# dsp.net
KiCad netlist of a schematic drawn in Altium Designer
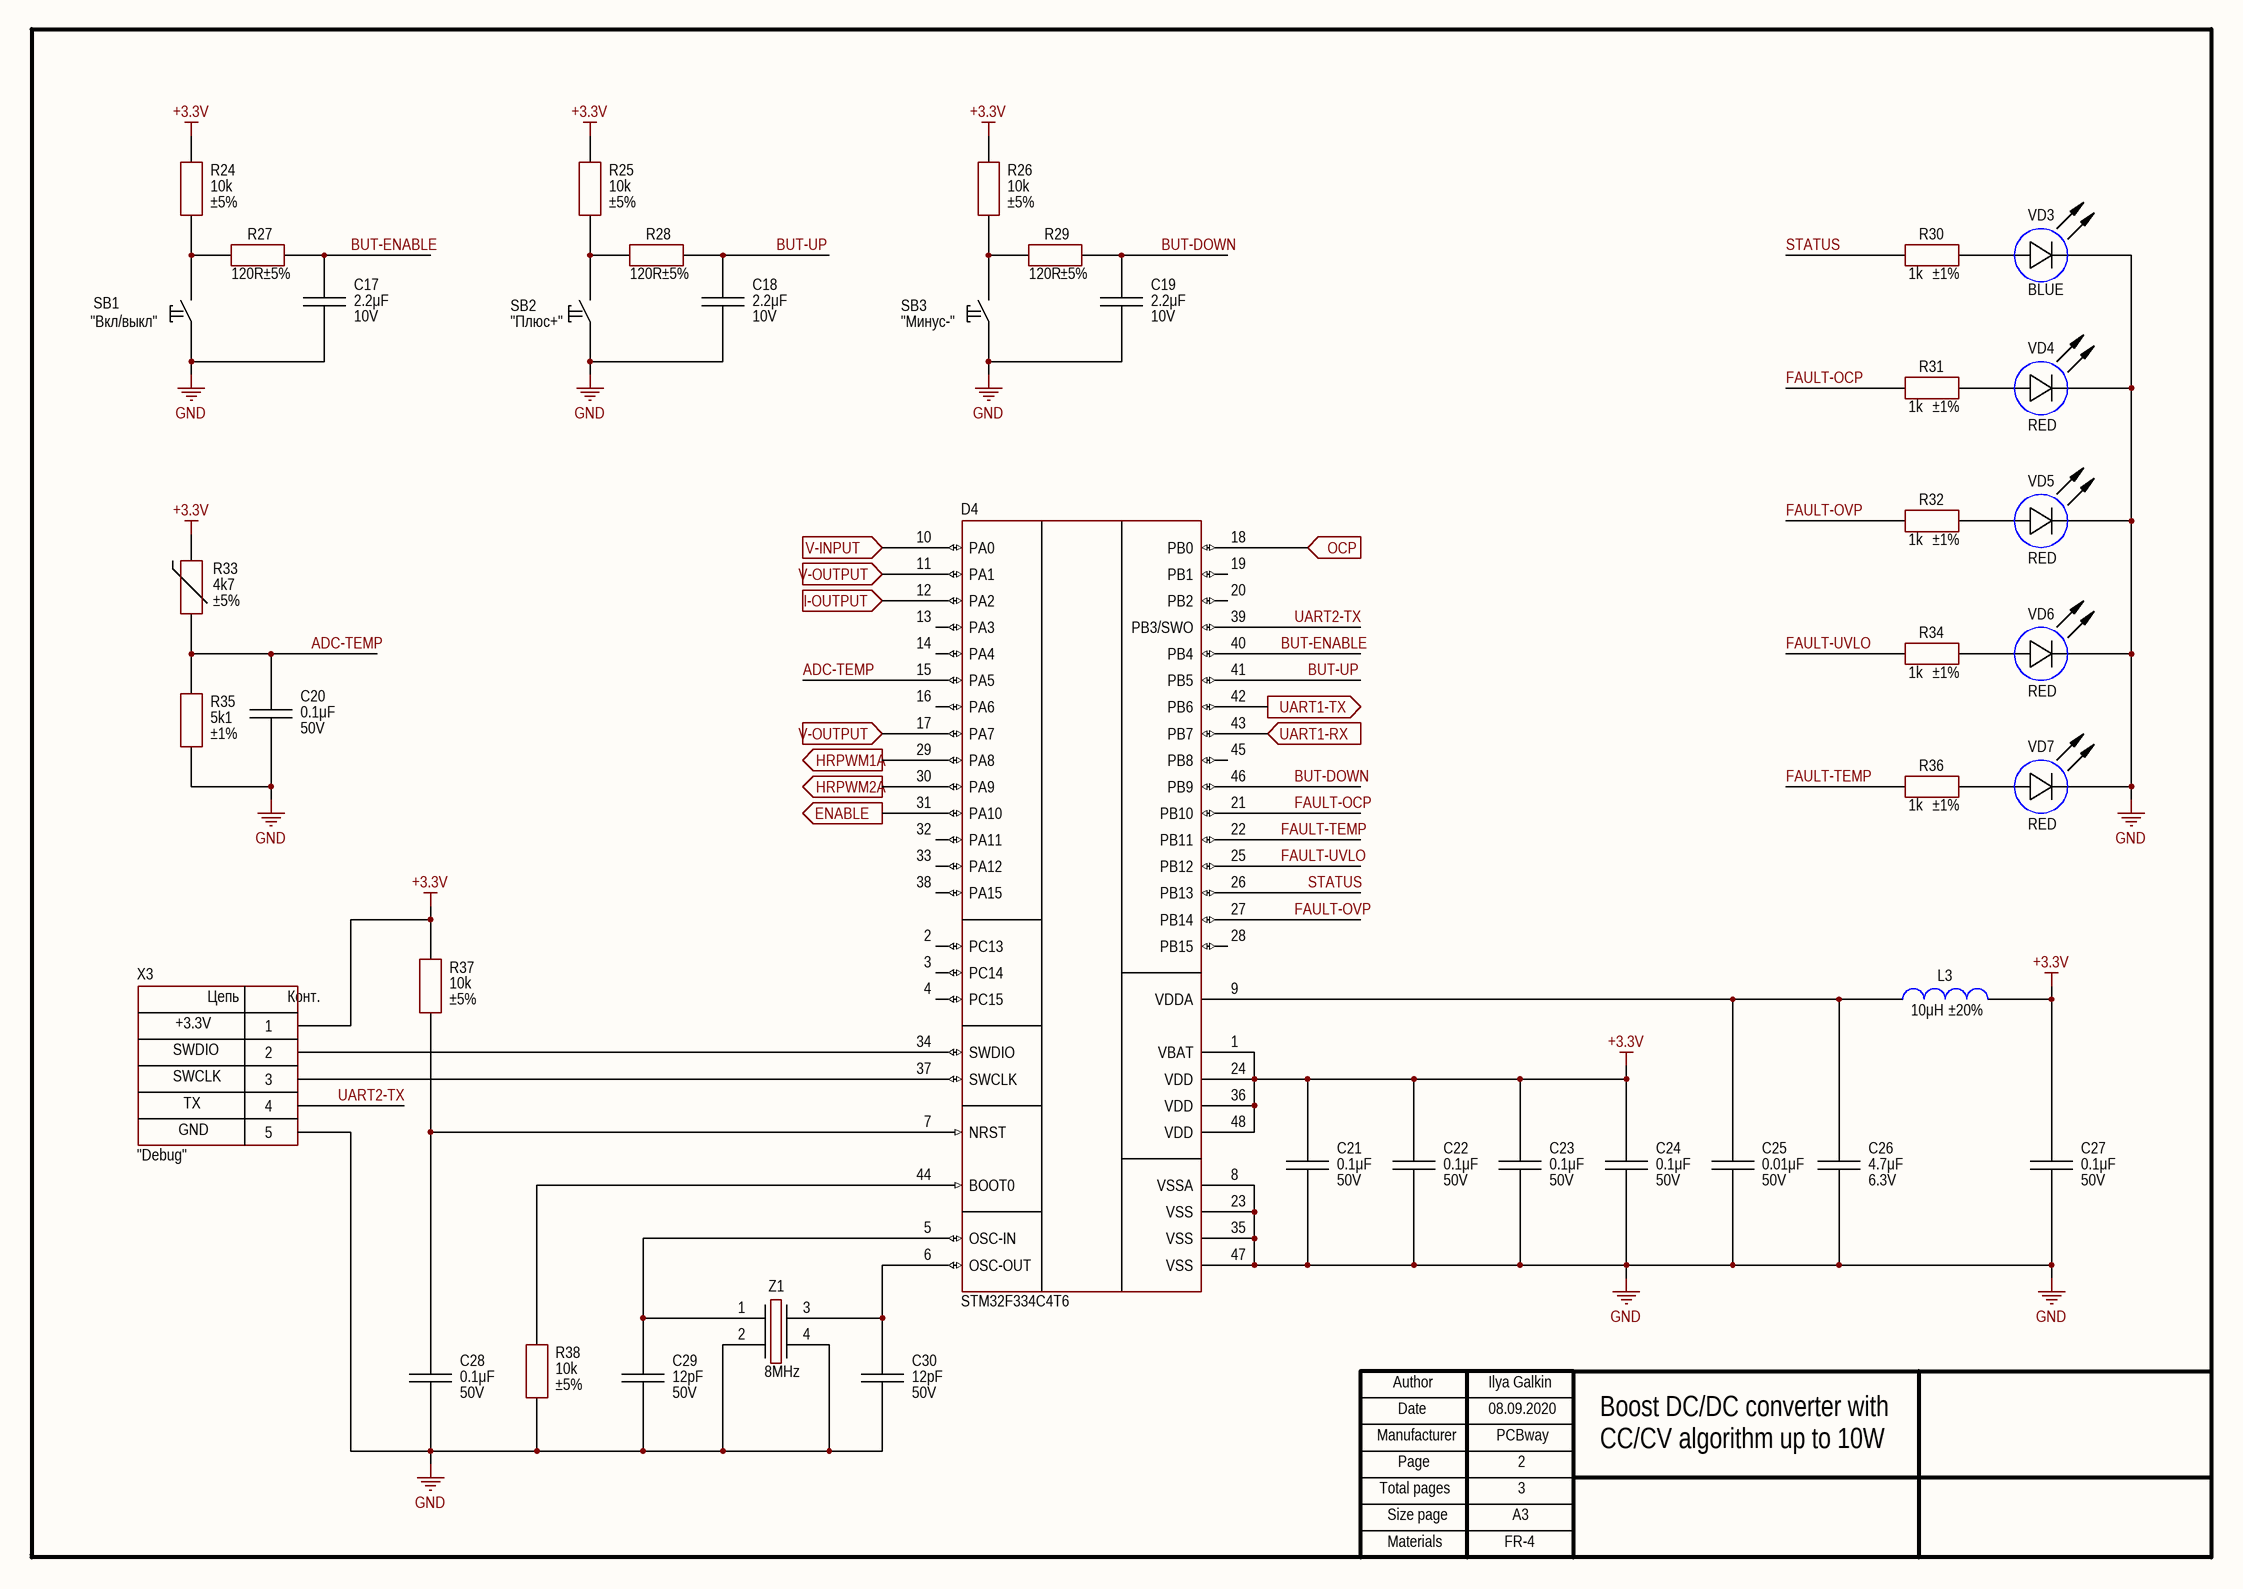
[diagram p0: dsp.SchDoc]

(export (version "E")
  (design (tool "Eeschema 10.0.6"))
  (components
    (comp (ref "C17")
      (value "2.2μF")
      (footprint "CAP: 0603")
      (fields
        (field (name "MANUFACTURER") "Samsung")
        (field (name "PARTNUMBER") "CL10B225KP8NFNC")
        (field (name "VALUEMANUFACTURERPARTNUMBER") "Ceramic capacitor, 2.2μF, X7R, ±10%, 10V, 0603, -55...+125°C")
        (field (name "VOLTAGE") "10V")
      )
      (libsource (lib "capacitor") (part "Ceramic_0603"))
    )
    (comp (ref "C18")
      (value "2.2μF")
      (footprint "CAP: 0603")
      (fields
        (field (name "MANUFACTURER") "Samsung")
        (field (name "PARTNUMBER") "CL10B225KP8NFNC")
        (field (name "VALUEMANUFACTURERPARTNUMBER") "Ceramic capacitor, 2.2μF, X7R, ±10%, 10V, 0603, -55...+125°C")
        (field (name "VOLTAGE") "10V")
      )
      (libsource (lib "capacitor") (part "Ceramic_0603"))
    )
    (comp (ref "C19")
      (value "2.2μF")
      (footprint "CAP: 0603")
      (fields
        (field (name "MANUFACTURER") "Samsung")
        (field (name "PARTNUMBER") "CL10B225KP8NFNC")
        (field (name "VALUEMANUFACTURERPARTNUMBER") "Ceramic capacitor, 2.2μF, X7R, ±10%, 10V, 0603, -55...+125°C")
        (field (name "VOLTAGE") "10V")
      )
      (libsource (lib "capacitor") (part "Ceramic_0603"))
    )
    (comp (ref "C20")
      (value "0.1μF")
      (footprint "CAP: 0603")
      (fields
        (field (name "MANUFACTURER") "Samsung")
        (field (name "PARTNUMBER") "CL10B104KB8NNNL")
        (field (name "VALUEMANUFACTURERPARTNUMBER") "Ceramic capacitor, 0.1μF, X7R, ±10%, 50V, 0603, -55...+125°C")
        (field (name "VOLTAGE") "50V")
      )
      (libsource (lib "capacitor") (part "Ceramic_0603"))
    )
    (comp (ref "C21")
      (value "0.1μF")
      (footprint "CAP: 0603")
      (fields
        (field (name "MANUFACTURER") "Samsung")
        (field (name "PARTNUMBER") "CL10B104KB8NNNL")
        (field (name "VALUEMANUFACTURERPARTNUMBER") "Ceramic capacitor, 0.1μF, X7R, ±10%, 50V, 0603, -55...+125°C")
        (field (name "VOLTAGE") "50V")
      )
      (libsource (lib "capacitor") (part "Ceramic_0603"))
    )
    (comp (ref "C22")
      (value "0.1μF")
      (footprint "CAP: 0603")
      (fields
        (field (name "MANUFACTURER") "Samsung")
        (field (name "PARTNUMBER") "CL10B104KB8NNNL")
        (field (name "VALUEMANUFACTURERPARTNUMBER") "Ceramic capacitor, 0.1μF, X7R, ±10%, 50V, 0603, -55...+125°C")
        (field (name "VOLTAGE") "50V")
      )
      (libsource (lib "capacitor") (part "Ceramic_0603"))
    )
    (comp (ref "C23")
      (value "0.1μF")
      (footprint "CAP: 0603")
      (fields
        (field (name "MANUFACTURER") "Samsung")
        (field (name "PARTNUMBER") "CL10B104KB8NNNL")
        (field (name "VALUEMANUFACTURERPARTNUMBER") "Ceramic capacitor, 0.1μF, X7R, ±10%, 50V, 0603, -55...+125°C")
        (field (name "VOLTAGE") "50V")
      )
      (libsource (lib "capacitor") (part "Ceramic_0603"))
    )
    (comp (ref "C24")
      (value "0.1μF")
      (footprint "CAP: 0603")
      (fields
        (field (name "MANUFACTURER") "Samsung")
        (field (name "PARTNUMBER") "CL10B104KB8NNNL")
        (field (name "VALUEMANUFACTURERPARTNUMBER") "Ceramic capacitor, 0.1μF, X7R, ±10%, 50V, 0603, -55...+125°C")
        (field (name "VOLTAGE") "50V")
      )
      (libsource (lib "capacitor") (part "Ceramic_0603"))
    )
    (comp (ref "C25")
      (value "0.01μF")
      (footprint "CAP: 0603")
      (fields
        (field (name "MANUFACTURER") "Samsung")
        (field (name "PARTNUMBER") "CL10B103KB8NNNC")
        (field (name "VALUEMANUFACTURERPARTNUMBER") "Ceramic capacitor, 0.01μF, X7R, ±10%, 50V, 0603, -55...+125°C")
        (field (name "VOLTAGE") "50V")
      )
      (libsource (lib "capacitor") (part "Ceramic_0603"))
    )
    (comp (ref "C26")
      (value "4.7μF")
      (footprint "CAP: 0603")
      (fields
        (field (name "MANUFACTURER") "Samsung")
        (field (name "PARTNUMBER") "CL10B475KQ8NQNC")
        (field (name "VALUEMANUFACTURERPARTNUMBER") "Ceramic capacitor, 4.7μF, X7R, ±10%, 6.3V, 0603, -55...+125°C")
        (field (name "VOLTAGE") "6.3V")
      )
      (libsource (lib "capacitor") (part "Ceramic_0603"))
    )
    (comp (ref "C27")
      (value "0.1μF")
      (footprint "CAP: 0603")
      (fields
        (field (name "MANUFACTURER") "Samsung")
        (field (name "PARTNUMBER") "CL10B104KB8NNNL")
        (field (name "VALUEMANUFACTURERPARTNUMBER") "Ceramic capacitor, 0.1μF, X7R, ±10%, 50V, 0603, -55...+125°C")
        (field (name "VOLTAGE") "50V")
      )
      (libsource (lib "capacitor") (part "Ceramic_0603"))
    )
    (comp (ref "C28")
      (value "0.1μF")
      (footprint "CAP: 0603")
      (fields
        (field (name "MANUFACTURER") "Samsung")
        (field (name "PARTNUMBER") "CL10B104KB8NNNL")
        (field (name "VALUEMANUFACTURERPARTNUMBER") "Ceramic capacitor, 0.1μF, X7R, ±10%, 50V, 0603, -55...+125°C")
        (field (name "VOLTAGE") "50V")
      )
      (libsource (lib "capacitor") (part "Ceramic_0603"))
    )
    (comp (ref "C29")
      (value "12pF")
      (footprint "CAP: 0603")
      (fields
        (field (name "MANUFACTURER") "Samsung")
        (field (name "PARTNUMBER") "CL10C120JB8NNNC")
        (field (name "VALUEMANUFACTURERPARTNUMBER") "Ceramic capacitor, 12pF, NPO, ±10%, 50V, 0603, -55...+125°C")
        (field (name "VOLTAGE") "50V")
      )
      (libsource (lib "Capacitor") (part "Ceramic_0603"))
    )
    (comp (ref "C30")
      (value "12pF")
      (footprint "CAP: 0603")
      (fields
        (field (name "MANUFACTURER") "Samsung")
        (field (name "PARTNUMBER") "CL10C120JB8NNNC")
        (field (name "VALUEMANUFACTURERPARTNUMBER") "Ceramic capacitor, 12pF, NPO, ±10%, 50V, 0603, -55...+125°C")
        (field (name "VOLTAGE") "50V")
      )
      (libsource (lib "Capacitor") (part "Ceramic_0603"))
    )
    (comp (ref "D4")
      (value "~")
      (footprint "48-LQFP")
      (description "Cortex-M4")
      (fields
        (field (name "MANUFACTURER") "STMicroelectronics")
        (field (name "VALUEMANUFACTURERPARTNUMBER") "IC microcontroller, 32-Bit, Cortex-M4, 72MHz, 64KB, 12KB, 2...3.6V, -40...+85°C, 48-LQFP")
        (field (name "PARTNUMBER") "STM32F334C4T6")
      )
      (libsource (lib "ic-mcu") (part "STM32F334C8T6"))
    )
    (comp (ref "L3")
      (value "10μH")
      (footprint "IND: 0603")
      (fields
        (field (name "MANUFACTURER") "Murata Electronics")
        (field (name "PARTNUMBER") "LQM18FN100M00D")
        (field (name "VALUEMANUFACTURERPARTNUMBER") "Fixed inductor, 10μH, ±20%, 0603, 50mA, -55...+125°C")
        (field (name "TOLERANCE") "±20%")
      )
      (libsource (lib "Inductor") (part "Inductor_0603"))
    )
    (comp (ref "R24")
      (value "10k")
      (footprint "RES: 0603")
      (fields
        (field (name "MANUFACTURER") "Yageo")
        (field (name "PARTNUMBER") "RC0603JR-0710KL")
        (field (name "VALUEMANUFACTURERPARTNUMBER") "Resistor film, 10k, ±5%, 0603, 0.1W, -55...+125°C")
        (field (name "TOLERANCE") "±5%")
      )
      (libsource (lib "resistor") (part "Resistor_0603"))
    )
    (comp (ref "R25")
      (value "10k")
      (footprint "RES: 0603")
      (fields
        (field (name "MANUFACTURER") "Yageo")
        (field (name "PARTNUMBER") "RC0603JR-0710KL")
        (field (name "VALUEMANUFACTURERPARTNUMBER") "Resistor film, 10k, ±5%, 0603, 0.1W, -55...+125°C")
        (field (name "TOLERANCE") "±5%")
      )
      (libsource (lib "resistor") (part "Resistor_0603"))
    )
    (comp (ref "R26")
      (value "10k")
      (footprint "RES: 0603")
      (fields
        (field (name "MANUFACTURER") "Yageo")
        (field (name "PARTNUMBER") "RC0603JR-0710KL")
        (field (name "VALUEMANUFACTURERPARTNUMBER") "Resistor film, 10k, ±5%, 0603, 0.1W, -55...+125°C")
        (field (name "TOLERANCE") "±5%")
      )
      (libsource (lib "resistor") (part "Resistor_0603"))
    )
    (comp (ref "R27")
      (value "120R")
      (footprint "RES: 0603")
      (fields
        (field (name "MANUFACTURER") "Yageo")
        (field (name "PARTNUMBER") "RC0603JR-07120RL")
        (field (name "VALUEMANUFACTURERPARTNUMBER") "Resistor film, 120R, ±5%, 0603, 0.1W, -55...+125°C")
        (field (name "TOLERANCE") "±5%")
      )
      (libsource (lib "") (part "Resistor_0603_1"))
    )
    (comp (ref "R28")
      (value "120R")
      (footprint "RES: 0603")
      (fields
        (field (name "MANUFACTURER") "Yageo")
        (field (name "PARTNUMBER") "RC0603JR-07120RL")
        (field (name "VALUEMANUFACTURERPARTNUMBER") "Resistor film, 120R, ±5%, 0603, 0.1W, -55...+125°C")
        (field (name "TOLERANCE") "±5%")
      )
      (libsource (lib "") (part "Resistor_0603_1"))
    )
    (comp (ref "R29")
      (value "120R")
      (footprint "RES: 0603")
      (fields
        (field (name "MANUFACTURER") "Yageo")
        (field (name "PARTNUMBER") "RC0603JR-07120RL")
        (field (name "VALUEMANUFACTURERPARTNUMBER") "Resistor film, 120R, ±5%, 0603, 0.1W, -55...+125°C")
        (field (name "TOLERANCE") "±5%")
      )
      (libsource (lib "") (part "Resistor_0603_1"))
    )
    (comp (ref "R30")
      (value "1k")
      (footprint "RES: 0603")
      (fields
        (field (name "MANUFACTURER") "Yageo")
        (field (name "PARTNUMBER") "RC0603FR-071KL")
        (field (name "VALUEMANUFACTURERPARTNUMBER") "Resistor film, 1k, ±1%, 0603, 0.1W, -55...+125°C")
        (field (name "TOLERANCE") "±1%")
      )
      (libsource (lib "") (part "Resistor_0603_1"))
    )
    (comp (ref "R31")
      (value "1k")
      (footprint "RES: 0603")
      (fields
        (field (name "MANUFACTURER") "Yageo")
        (field (name "PARTNUMBER") "RC0603FR-071KL")
        (field (name "VALUEMANUFACTURERPARTNUMBER") "Resistor film, 1k, ±1%, 0603, 0.1W, -55...+125°C")
        (field (name "TOLERANCE") "±1%")
      )
      (libsource (lib "") (part "Resistor_0603_1"))
    )
    (comp (ref "R32")
      (value "1k")
      (footprint "RES: 0603")
      (fields
        (field (name "MANUFACTURER") "Yageo")
        (field (name "PARTNUMBER") "RC0603FR-071KL")
        (field (name "VALUEMANUFACTURERPARTNUMBER") "Resistor film, 1k, ±1%, 0603, 0.1W, -55...+125°C")
        (field (name "TOLERANCE") "±1%")
      )
      (libsource (lib "") (part "Resistor_0603_1"))
    )
    (comp (ref "R33")
      (value "4k7")
      (footprint "RES: 0603")
      (fields
        (field (name "MANUFACTURER") "Murata")
        (field (name "PARTNUMBER") "NCP18XM472J03RB")
        (field (name "VALUEMANUFACTURERPARTNUMBER") "NTC resistor, 4k7, ±5%, 0603, 3500K, -55...+125°C")
        (field (name "TOLERANCE") "±5%")
      )
      (libsource (lib "resistor") (part "NTC"))
    )
    (comp (ref "R34")
      (value "1k")
      (footprint "RES: 0603")
      (fields
        (field (name "MANUFACTURER") "Yageo")
        (field (name "PARTNUMBER") "RC0603FR-071KL")
        (field (name "VALUEMANUFACTURERPARTNUMBER") "Resistor film, 1k, ±1%, 0603, 0.1W, -55...+125°C")
        (field (name "TOLERANCE") "±1%")
      )
      (libsource (lib "") (part "Resistor_0603_1"))
    )
    (comp (ref "R35")
      (value "5k1")
      (footprint "RES: 0603")
      (fields
        (field (name "MANUFACTURER") "Yageo")
        (field (name "PARTNUMBER") "RC0603FR-075K1L")
        (field (name "VALUEMANUFACTURERPARTNUMBER") "Resistor film, 5k1, ±1%, 0603, 0.1W, -55...+125°C")
        (field (name "TOLERANCE") "±1%")
      )
      (libsource (lib "resistor") (part "Resistor_0603"))
    )
    (comp (ref "R36")
      (value "1k")
      (footprint "RES: 0603")
      (fields
        (field (name "MANUFACTURER") "Yageo")
        (field (name "PARTNUMBER") "RC0603FR-071KL")
        (field (name "VALUEMANUFACTURERPARTNUMBER") "Resistor film, 1k, ±1%, 0603, 0.1W, -55...+125°C")
        (field (name "TOLERANCE") "±1%")
      )
      (libsource (lib "") (part "Resistor_0603_1"))
    )
    (comp (ref "R37")
      (value "10k")
      (footprint "RES: 0603")
      (fields
        (field (name "MANUFACTURER") "Yageo")
        (field (name "PARTNUMBER") "RC0603JR-0710KL")
        (field (name "VALUEMANUFACTURERPARTNUMBER") "Resistor film, 10k, ±5%, 0603, 0.1W, -55...+125°C")
        (field (name "TOLERANCE") "±5%")
      )
      (libsource (lib "resistor") (part "Resistor_0603"))
    )
    (comp (ref "R38")
      (value "10k")
      (footprint "RES: 0603")
      (fields
        (field (name "MANUFACTURER") "Yageo")
        (field (name "PARTNUMBER") "RC0603JR-0710KL")
        (field (name "VALUEMANUFACTURERPARTNUMBER") "Resistor film, 10k, ±5%, 0603, 0.1W, -55...+125°C")
        (field (name "TOLERANCE") "±5%")
      )
      (libsource (lib "resistor") (part "Resistor_0603"))
    )
    (comp (ref "SB1")
      (value "~")
      (footprint "BUT: 6x3.5 SMD")
      (fields
        (field (name "MANUFACTURER") "C&K")
        (field (name "VALUEMANUFACTURERPARTNUMBER") "Tactile button, 6x3.5mm")
        (field (name "PARTNUMBER") "PTS636 SM43")
        (field (name "COMMENTTEXT") "\"Вкл/выкл\"")
      )
      (libsource (lib "electromechanics") (part "Button_tactile"))
    )
    (comp (ref "SB2")
      (value "~")
      (footprint "BUT: 6x3.5 SMD")
      (fields
        (field (name "MANUFACTURER") "C&K")
        (field (name "VALUEMANUFACTURERPARTNUMBER") "Tactile button, 6x3.5mm")
        (field (name "PARTNUMBER") "PTS636 SM43")
        (field (name "COMMENTTEXT") "\"Плюс+\"")
      )
      (libsource (lib "electromechanics") (part "Button_tactile"))
    )
    (comp (ref "SB3")
      (value "~")
      (footprint "BUT: 6x3.5 SMD")
      (fields
        (field (name "MANUFACTURER") "C&K")
        (field (name "VALUEMANUFACTURERPARTNUMBER") "Tactile button, 6x3.5mm")
        (field (name "PARTNUMBER") "PTS636 SM43")
        (field (name "COMMENTTEXT") "\"Минус-\"")
      )
      (libsource (lib "electromechanics") (part "Button_tactile"))
    )
    (comp (ref "VD3")
      (value "~")
      (footprint "LED: 0603B")
      (fields
        (field (name "MANUFACTURER") "Wurth")
        (field (name "VALUEMANUFACTURERPARTNUMBER") "LED, 20mA, 3.2V, 0603, -55...+150°C")
        (field (name "PARTNUMBER") "150060BS75000")
        (field (name "COLOR") "BLUE")
      )
      (libsource (lib "Diode") (part "LED_single"))
    )
    (comp (ref "VD4")
      (value "~")
      (footprint "LED: 0603R")
      (fields
        (field (name "MANUFACTURER") "Wurth")
        (field (name "VALUEMANUFACTURERPARTNUMBER") "LED, 20 mA, 2V, 0603, -55...+150°C")
        (field (name "PARTNUMBER") "150060RS75000")
        (field (name "COLOR") "RED")
      )
      (libsource (lib "Diode") (part "LED_single"))
    )
    (comp (ref "VD5")
      (value "~")
      (footprint "LED: 0603R")
      (fields
        (field (name "MANUFACTURER") "Wurth")
        (field (name "VALUEMANUFACTURERPARTNUMBER") "LED, 20 mA, 2V, 0603, -55...+150°C")
        (field (name "PARTNUMBER") "150060RS75000")
        (field (name "COLOR") "RED")
      )
      (libsource (lib "Diode") (part "LED_single"))
    )
    (comp (ref "VD6")
      (value "~")
      (footprint "LED: 0603R")
      (fields
        (field (name "MANUFACTURER") "Wurth")
        (field (name "VALUEMANUFACTURERPARTNUMBER") "LED, 20 mA, 2V, 0603, -55...+150°C")
        (field (name "PARTNUMBER") "150060RS75000")
        (field (name "COLOR") "RED")
      )
      (libsource (lib "Diode") (part "LED_single"))
    )
    (comp (ref "VD7")
      (value "~")
      (footprint "LED: 0603R")
      (fields
        (field (name "MANUFACTURER") "Wurth")
        (field (name "VALUEMANUFACTURERPARTNUMBER") "LED, 20 mA, 2V, 0603, -55...+150°C")
        (field (name "PARTNUMBER") "150060RS75000")
        (field (name "COLOR") "RED")
      )
      (libsource (lib "Diode") (part "LED_single"))
    )
    (comp (ref "X3")
      (value "~")
      (footprint "CON: SM05B-GHS")
      (fields
        (field (name "MANUFACTURER") "JST")
        (field (name "VALUEMANUFACTURERPARTNUMBER") "Connector, 5pin, 1.25mm, 50VDC, 1A")
        (field (name "PARTNUMBER") "SM05B-GHS")
        (field (name "COMMENTTEXT") "\"Debug\"")
      )
      (libsource (lib "Connector") (part "Connector_SM05B"))
    )
    (comp (ref "Z1")
      (value "~")
      (footprint "OSC: 3225")
      (fields
        (field (name "MANUFACTURER") "ECS")
        (field (name "PARTNUMBER") "ECS-80-12-33-JGN-TR")
        (field (name "VALUEMANUFACTURERPARTNUMBER") "Crystal, 8MHz, 12pF, ±30ppm, case 3225, -40...+85°C")
        (field (name "FREQUENCY") "8MHz")
      )
      (libsource (lib "Oscilator") (part "Crystal_3225"))
    )
  )
  (nets
    (net (code "1") (name "+3.3V") (class "Default")
      (node (ref "C21") (pin "2") (pinfunction "2_2") (pintype "passive"))
      (node (ref "C22") (pin "2") (pinfunction "2_2") (pintype "passive"))
      (node (ref "C23") (pin "2") (pinfunction "2_2") (pintype "passive"))
      (node (ref "C24") (pin "2") (pinfunction "2_2") (pintype "passive"))
      (node (ref "C27") (pin "2") (pinfunction "2_2") (pintype "passive"))
      (node (ref "D4") (pin "1") (pinfunction "VBAT_1") (pintype "passive"))
      (node (ref "D4") (pin "24") (pinfunction "VDD_24") (pintype "passive"))
      (node (ref "D4") (pin "36") (pinfunction "VDD_36") (pintype "passive"))
      (node (ref "D4") (pin "48") (pinfunction "VDD_48") (pintype "passive"))
      (node (ref "L3") (pin "1") (pinfunction "1_1") (pintype "passive"))
      (node (ref "R24") (pin "2") (pinfunction "2_2") (pintype "passive"))
      (node (ref "R25") (pin "2") (pinfunction "2_2") (pintype "passive"))
      (node (ref "R26") (pin "2") (pinfunction "2_2") (pintype "passive"))
      (node (ref "R33") (pin "2") (pinfunction "2_2") (pintype "passive"))
      (node (ref "R37") (pin "2") (pinfunction "2_2") (pintype "passive"))
      (node (ref "X3") (pin "1") (pinfunction "1_1") (pintype "passive"))
    )
    (net (code "2") (name "/ADC-TEMP") (class "Default")
      (node (ref "C20") (pin "2") (pinfunction "2_2") (pintype "passive"))
      (node (ref "D4") (pin "15") (pinfunction "PA5_15") (pintype "bidirectional"))
      (node (ref "R33") (pin "1") (pinfunction "1_1") (pintype "passive"))
      (node (ref "R35") (pin "2") (pinfunction "2_2") (pintype "passive"))
    )
    (net (code "3") (name "/BUT-DOWN") (class "Default")
      (node (ref "C19") (pin "2") (pinfunction "2_2") (pintype "passive"))
      (node (ref "D4") (pin "46") (pinfunction "PB9_46") (pintype "bidirectional"))
      (node (ref "R29") (pin "2") (pinfunction "2_2") (pintype "passive"))
    )
    (net (code "4") (name "/BUT-ENABLE") (class "Default")
      (node (ref "C17") (pin "2") (pinfunction "2_2") (pintype "passive"))
      (node (ref "D4") (pin "40") (pinfunction "PB4_40") (pintype "bidirectional"))
      (node (ref "R27") (pin "2") (pinfunction "2_2") (pintype "passive"))
    )
    (net (code "5") (name "/BUT-UP") (class "Default")
      (node (ref "C18") (pin "2") (pinfunction "2_2") (pintype "passive"))
      (node (ref "D4") (pin "41") (pinfunction "PB5_41") (pintype "bidirectional"))
      (node (ref "R28") (pin "2") (pinfunction "2_2") (pintype "passive"))
    )
    (net (code "6") (name "/ENABLE") (class "Default")
      (node (ref "D4") (pin "31") (pinfunction "PA10_31") (pintype "bidirectional"))
    )
    (net (code "7") (name "/FAULT-OCP") (class "Default")
      (node (ref "D4") (pin "21") (pinfunction "PB10_21") (pintype "bidirectional"))
      (node (ref "R31") (pin "1") (pinfunction "1_1") (pintype "passive"))
    )
    (net (code "8") (name "/FAULT-OVP") (class "Default")
      (node (ref "D4") (pin "27") (pinfunction "PB14_27") (pintype "bidirectional"))
      (node (ref "R32") (pin "1") (pinfunction "1_1") (pintype "passive"))
    )
    (net (code "9") (name "/FAULT-TEMP") (class "Default")
      (node (ref "D4") (pin "22") (pinfunction "PB11_22") (pintype "bidirectional"))
      (node (ref "R36") (pin "1") (pinfunction "1_1") (pintype "passive"))
    )
    (net (code "10") (name "/FAULT-UVLO") (class "Default")
      (node (ref "D4") (pin "25") (pinfunction "PB12_25") (pintype "bidirectional"))
      (node (ref "R34") (pin "1") (pinfunction "1_1") (pintype "passive"))
    )
    (net (code "11") (name "/HRPWM1A") (class "Default")
      (node (ref "D4") (pin "29") (pinfunction "PA8_29") (pintype "bidirectional"))
    )
    (net (code "12") (name "/HRPWM2A") (class "Default")
      (node (ref "D4") (pin "30") (pinfunction "PA9_30") (pintype "bidirectional"))
    )
    (net (code "13") (name "/I-OUTPUT") (class "Default")
      (node (ref "D4") (pin "12") (pinfunction "PA2_12") (pintype "bidirectional"))
    )
    (net (code "14") (name "/OCP") (class "Default")
      (node (ref "D4") (pin "18") (pinfunction "PB0_18") (pintype "bidirectional"))
    )
    (net (code "15") (name "/STATUS") (class "Default")
      (node (ref "D4") (pin "26") (pinfunction "PB13_26") (pintype "bidirectional"))
      (node (ref "R30") (pin "1") (pinfunction "1_1") (pintype "passive"))
    )
    (net (code "16") (name "/UART1-RX") (class "Default")
      (node (ref "D4") (pin "43") (pinfunction "PB7_43") (pintype "bidirectional"))
    )
    (net (code "17") (name "/UART1-TX") (class "Default")
      (node (ref "D4") (pin "42") (pinfunction "PB6_42") (pintype "bidirectional"))
    )
    (net (code "18") (name "/UART2-TX") (class "Default")
      (node (ref "D4") (pin "39") (pinfunction "PB3/SWO_39") (pintype "bidirectional"))
      (node (ref "X3") (pin "4") (pinfunction "4_4") (pintype "power_in"))
    )
    (net (code "19") (name "/V-INPUT") (class "Default")
      (node (ref "D4") (pin "10") (pinfunction "PA0_10") (pintype "bidirectional"))
    )
    (net (code "20") (name "/V-OUTPUT") (class "Default")
      (node (ref "D4") (pin "11") (pinfunction "PA1_11") (pintype "bidirectional"))
      (node (ref "D4") (pin "17") (pinfunction "PA7_17") (pintype "bidirectional"))
    )
    (net (code "21") (name "GND") (class "Default")
      (node (ref "C17") (pin "1") (pinfunction "1_1") (pintype "passive"))
      (node (ref "C18") (pin "1") (pinfunction "1_1") (pintype "passive"))
      (node (ref "C19") (pin "1") (pinfunction "1_1") (pintype "passive"))
      (node (ref "C20") (pin "1") (pinfunction "1_1") (pintype "passive"))
      (node (ref "C21") (pin "1") (pinfunction "1_1") (pintype "passive"))
      (node (ref "C22") (pin "1") (pinfunction "1_1") (pintype "passive"))
      (node (ref "C23") (pin "1") (pinfunction "1_1") (pintype "passive"))
      (node (ref "C24") (pin "1") (pinfunction "1_1") (pintype "passive"))
      (node (ref "C25") (pin "1") (pinfunction "1_1") (pintype "passive"))
      (node (ref "C26") (pin "1") (pinfunction "1_1") (pintype "passive"))
      (node (ref "C27") (pin "1") (pinfunction "1_1") (pintype "passive"))
      (node (ref "C28") (pin "1") (pinfunction "1_1") (pintype "passive"))
      (node (ref "C29") (pin "1") (pinfunction "1_1") (pintype "power_in"))
      (node (ref "C30") (pin "1") (pinfunction "1_1") (pintype "power_in"))
      (node (ref "D4") (pin "23") (pinfunction "VSS_23") (pintype "passive"))
      (node (ref "D4") (pin "35") (pinfunction "VSS_35") (pintype "passive"))
      (node (ref "D4") (pin "47") (pinfunction "VSS_47") (pintype "passive"))
      (node (ref "D4") (pin "8") (pinfunction "VSSA_8") (pintype "passive"))
      (node (ref "R35") (pin "1") (pinfunction "1_1") (pintype "passive"))
      (node (ref "R38") (pin "1") (pinfunction "1_1") (pintype "passive"))
      (node (ref "SB1") (pin "1") (pinfunction "1_1") (pintype "passive"))
      (node (ref "SB2") (pin "1") (pinfunction "1_1") (pintype "passive"))
      (node (ref "SB3") (pin "1") (pinfunction "1_1") (pintype "passive"))
      (node (ref "VD3") (pin "2") (pinfunction "C_2") (pintype "passive"))
      (node (ref "VD4") (pin "2") (pinfunction "C_2") (pintype "passive"))
      (node (ref "VD5") (pin "2") (pinfunction "C_2") (pintype "passive"))
      (node (ref "VD6") (pin "2") (pinfunction "C_2") (pintype "passive"))
      (node (ref "VD7") (pin "2") (pinfunction "C_2") (pintype "passive"))
      (node (ref "X3") (pin "5") (pinfunction "5_5") (pintype "power_in"))
      (node (ref "Z1") (pin "2") (pinfunction "2_2") (pintype "passive"))
      (node (ref "Z1") (pin "4") (pinfunction "4_4") (pintype "passive"))
    )
    (net (code "22") (name "Net-(D4-BOOT0)") (class "Default")
      (node (ref "D4") (pin "44") (pinfunction "BOOT0_44") (pintype "input"))
      (node (ref "R38") (pin "2") (pinfunction "2_2") (pintype "passive"))
    )
    (net (code "23") (name "Net-(D4-NRST)") (class "Default")
      (node (ref "C28") (pin "2") (pinfunction "2_2") (pintype "passive"))
      (node (ref "D4") (pin "7") (pinfunction "NRST_7") (pintype "input"))
      (node (ref "R37") (pin "1") (pinfunction "1_1") (pintype "passive"))
    )
    (net (code "24") (name "Net-(D4-OSC-IN)") (class "Default")
      (node (ref "C29") (pin "2") (pinfunction "2_2") (pintype "power_in"))
      (node (ref "D4") (pin "5") (pinfunction "OSC-IN_5") (pintype "bidirectional"))
      (node (ref "Z1") (pin "1") (pinfunction "1_1") (pintype "passive"))
    )
    (net (code "25") (name "Net-(D4-OSC-OUT)") (class "Default")
      (node (ref "C30") (pin "2") (pinfunction "2_2") (pintype "power_in"))
      (node (ref "D4") (pin "6") (pinfunction "OSC-OUT_6") (pintype "bidirectional"))
      (node (ref "Z1") (pin "3") (pinfunction "3_3") (pintype "passive"))
    )
    (net (code "26") (name "Net-(D4-SWCLK)") (class "Default")
      (node (ref "D4") (pin "37") (pinfunction "SWCLK_37") (pintype "bidirectional"))
      (node (ref "X3") (pin "3") (pinfunction "3_3") (pintype "power_in"))
    )
    (net (code "27") (name "Net-(D4-SWDIO)") (class "Default")
      (node (ref "D4") (pin "34") (pinfunction "SWDIO_34") (pintype "bidirectional"))
      (node (ref "X3") (pin "2") (pinfunction "2_2") (pintype "passive"))
    )
    (net (code "28") (name "Net-(D4-VDDA)") (class "Default")
      (node (ref "C25") (pin "2") (pinfunction "2_2") (pintype "passive"))
      (node (ref "C26") (pin "2") (pinfunction "2_2") (pintype "passive"))
      (node (ref "D4") (pin "9") (pinfunction "VDDA_9") (pintype "passive"))
      (node (ref "L3") (pin "2") (pinfunction "2_2") (pintype "passive"))
    )
    (net (code "29") (name "Net-(R24-Pad1)") (class "Default")
      (node (ref "R24") (pin "1") (pinfunction "1_1") (pintype "passive"))
      (node (ref "R27") (pin "1") (pinfunction "1_1") (pintype "passive"))
      (node (ref "SB1") (pin "2") (pinfunction "2_2") (pintype "passive"))
    )
    (net (code "30") (name "Net-(R25-Pad1)") (class "Default")
      (node (ref "R25") (pin "1") (pinfunction "1_1") (pintype "passive"))
      (node (ref "R28") (pin "1") (pinfunction "1_1") (pintype "passive"))
      (node (ref "SB2") (pin "2") (pinfunction "2_2") (pintype "passive"))
    )
    (net (code "31") (name "Net-(R26-Pad1)") (class "Default")
      (node (ref "R26") (pin "1") (pinfunction "1_1") (pintype "passive"))
      (node (ref "R29") (pin "1") (pinfunction "1_1") (pintype "passive"))
      (node (ref "SB3") (pin "2") (pinfunction "2_2") (pintype "passive"))
    )
    (net (code "32") (name "Net-(VD3-A)") (class "Default")
      (node (ref "R30") (pin "2") (pinfunction "2_2") (pintype "passive"))
      (node (ref "VD3") (pin "1") (pinfunction "A_1") (pintype "passive"))
    )
    (net (code "33") (name "Net-(VD4-A)") (class "Default")
      (node (ref "R31") (pin "2") (pinfunction "2_2") (pintype "passive"))
      (node (ref "VD4") (pin "1") (pinfunction "A_1") (pintype "passive"))
    )
    (net (code "34") (name "Net-(VD5-A)") (class "Default")
      (node (ref "R32") (pin "2") (pinfunction "2_2") (pintype "passive"))
      (node (ref "VD5") (pin "1") (pinfunction "A_1") (pintype "passive"))
    )
    (net (code "35") (name "Net-(VD6-A)") (class "Default")
      (node (ref "R34") (pin "2") (pinfunction "2_2") (pintype "passive"))
      (node (ref "VD6") (pin "1") (pinfunction "A_1") (pintype "passive"))
    )
    (net (code "36") (name "Net-(VD7-A)") (class "Default")
      (node (ref "R36") (pin "2") (pinfunction "2_2") (pintype "passive"))
      (node (ref "VD7") (pin "1") (pinfunction "A_1") (pintype "passive"))
    )
    (net (code "37") (name "unconnected-(D4-PA3-Pad13)") (class "Default")
      (node (ref "D4") (pin "13") (pinfunction "PA3_13") (pintype "bidirectional"))
    )
    (net (code "38") (name "unconnected-(D4-PA4-Pad14)") (class "Default")
      (node (ref "D4") (pin "14") (pinfunction "PA4_14") (pintype "bidirectional"))
    )
    (net (code "39") (name "unconnected-(D4-PA6-Pad16)") (class "Default")
      (node (ref "D4") (pin "16") (pinfunction "PA6_16") (pintype "bidirectional"))
    )
    (net (code "40") (name "unconnected-(D4-PA11-Pad32)") (class "Default")
      (node (ref "D4") (pin "32") (pinfunction "PA11_32") (pintype "bidirectional"))
    )
    (net (code "41") (name "unconnected-(D4-PA12-Pad33)") (class "Default")
      (node (ref "D4") (pin "33") (pinfunction "PA12_33") (pintype "bidirectional"))
    )
    (net (code "42") (name "unconnected-(D4-PA15-Pad38)") (class "Default")
      (node (ref "D4") (pin "38") (pinfunction "PA15_38") (pintype "bidirectional"))
    )
    (net (code "43") (name "unconnected-(D4-PB1-Pad19)") (class "Default")
      (node (ref "D4") (pin "19") (pinfunction "PB1_19") (pintype "bidirectional"))
    )
    (net (code "44") (name "unconnected-(D4-PB2-Pad20)") (class "Default")
      (node (ref "D4") (pin "20") (pinfunction "PB2_20") (pintype "bidirectional"))
    )
    (net (code "45") (name "unconnected-(D4-PB8-Pad45)") (class "Default")
      (node (ref "D4") (pin "45") (pinfunction "PB8_45") (pintype "bidirectional"))
    )
    (net (code "46") (name "unconnected-(D4-PB15-Pad28)") (class "Default")
      (node (ref "D4") (pin "28") (pinfunction "PB15_28") (pintype "bidirectional"))
    )
    (net (code "47") (name "unconnected-(D4-PC13-Pad2)") (class "Default")
      (node (ref "D4") (pin "2") (pinfunction "PC13_2") (pintype "bidirectional"))
    )
    (net (code "48") (name "unconnected-(D4-PC14-Pad3)") (class "Default")
      (node (ref "D4") (pin "3") (pinfunction "PC14_3") (pintype "bidirectional"))
    )
    (net (code "49") (name "unconnected-(D4-PC15-Pad4)") (class "Default")
      (node (ref "D4") (pin "4") (pinfunction "PC15_4") (pintype "bidirectional"))
    )
  )
)
